# MRv2.net
KiCad netlist of a schematic drawn in Altium Designer
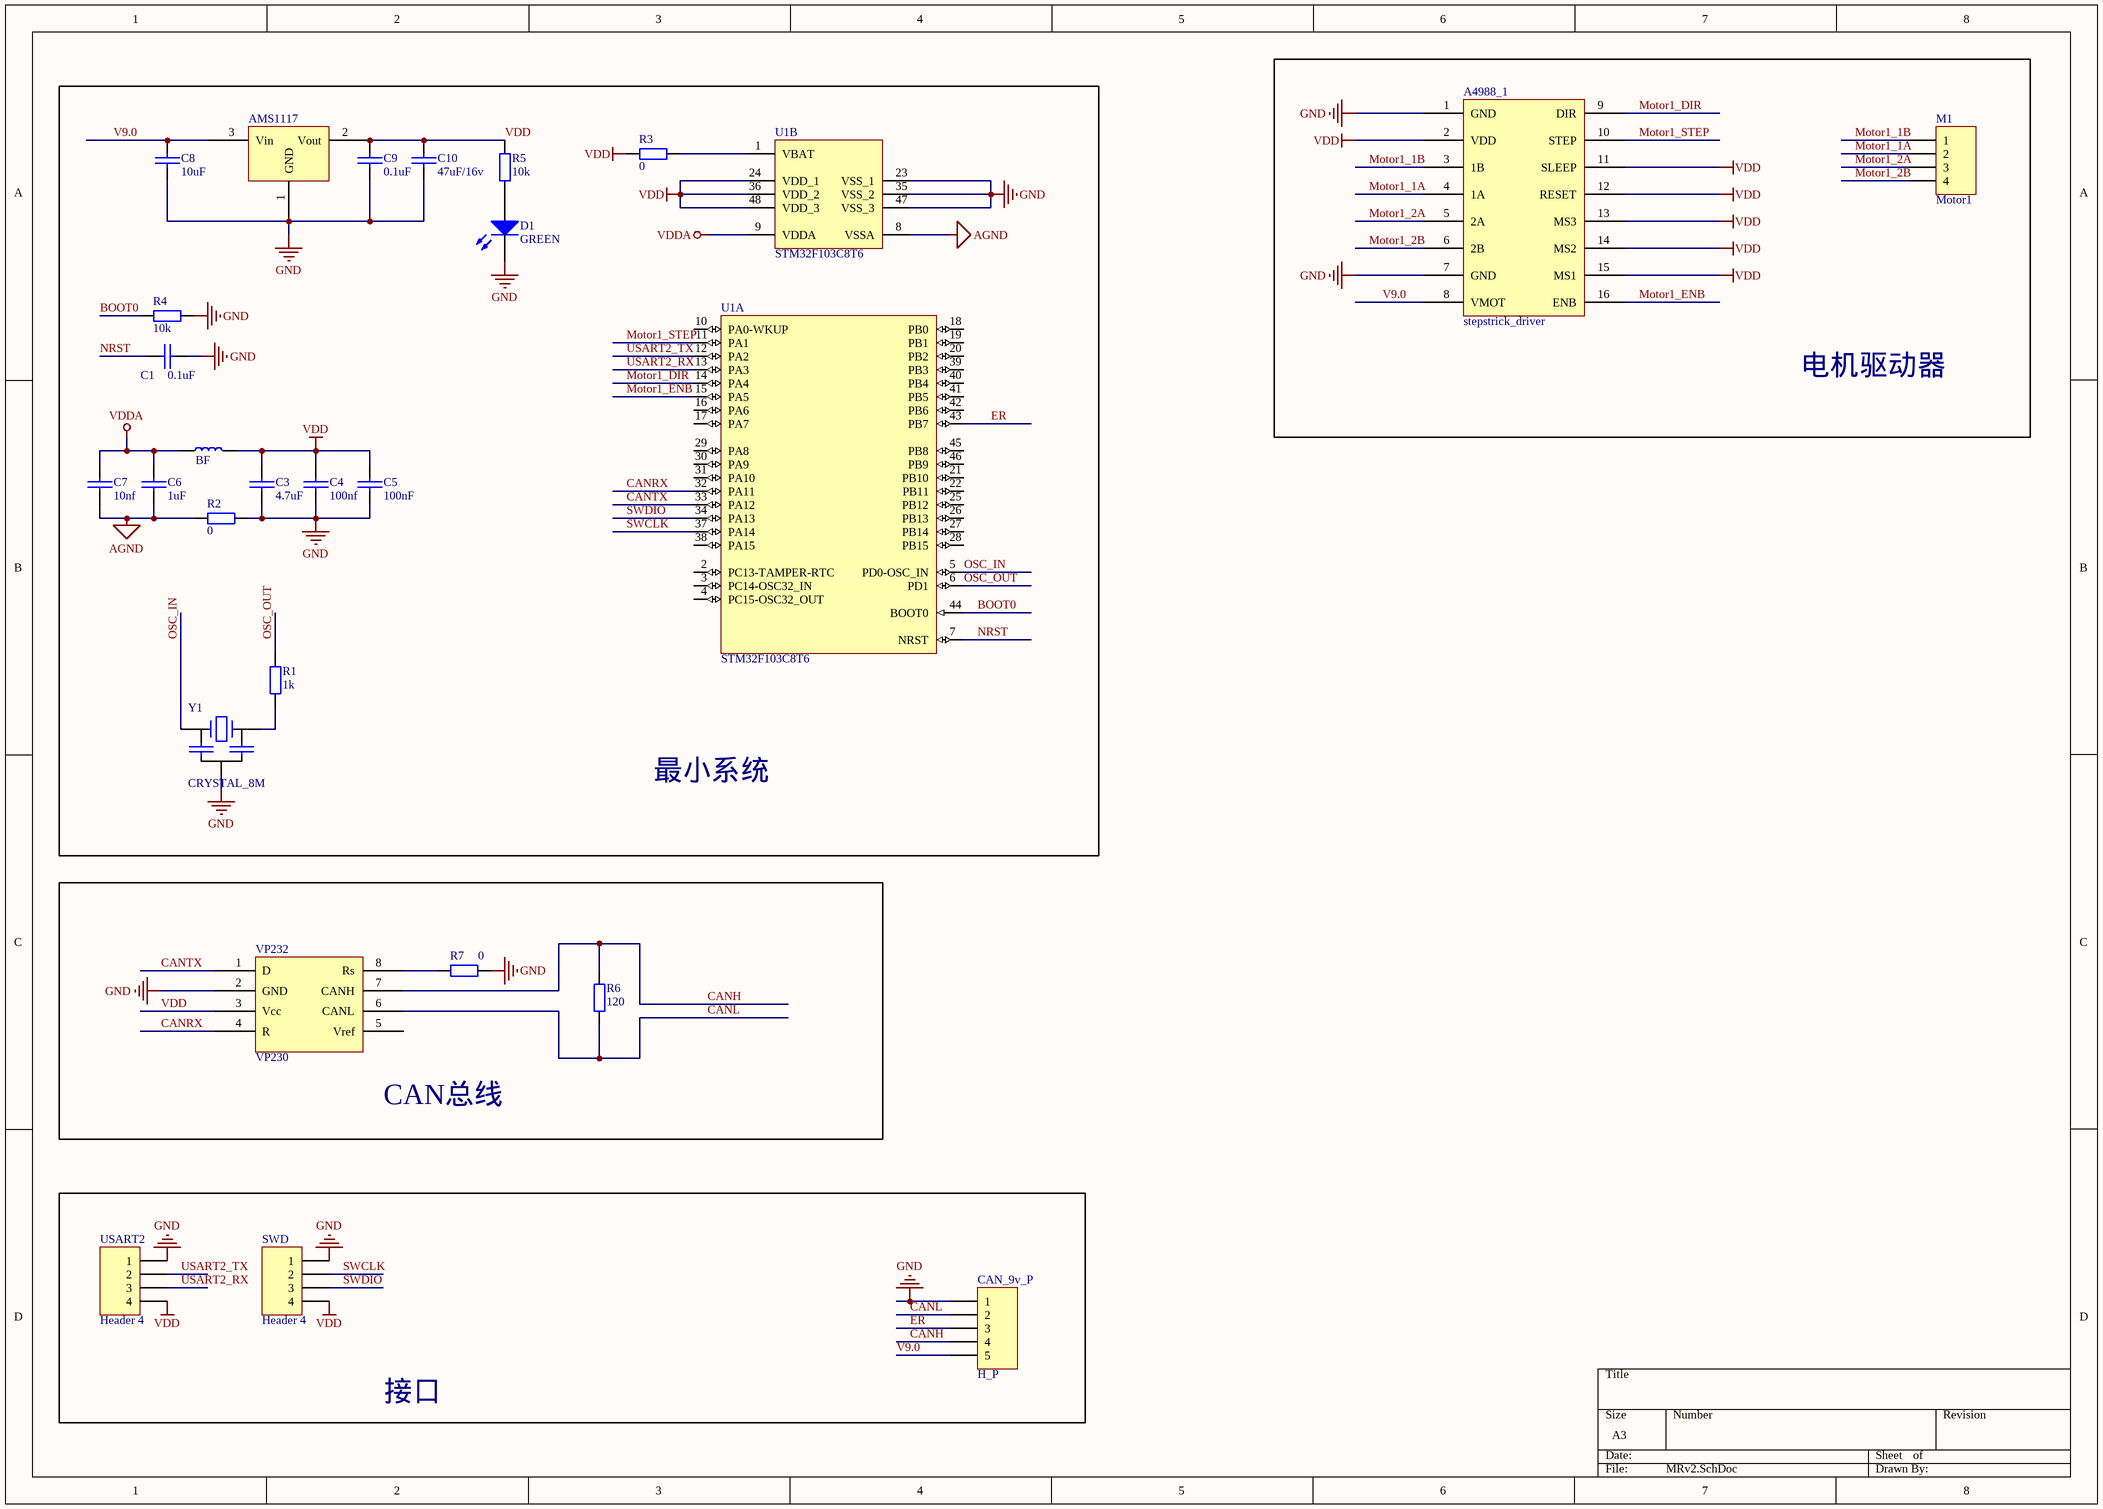
[diagram p0: MRv2.SchDoc]

(export (version "E")
  (design (tool "Eeschema 10.0.6"))
  (components
    (comp (ref "A4988_1")
      (value "stepstrick_driver")
      (footprint "A4988")
      (libsource (lib "ZYX") (part "stepstrick_driver"))
    )
    (comp (ref "AMS1117") (value "ASM1117") (footprint "SOT223") (libsource (lib "ZYX") (part "ASM1117")))
    (comp (ref "BF")
      (value "BF")
      (footprint "R1608[0603]")
      (description "磁珠")
      (libsource (lib "SkyWorks2") (part "BF"))
    )
    (comp (ref "C1")
      (value "0.1uF")
      (footprint "C1608[0603]N")
      (description "贴片无极性电容")
      (fields (field (name "Comment") "cap smd"))
      (libsource (lib "SkyWorks") (part "CAP"))
    )
    (comp (ref "C3")
      (value "4.7uF")
      (footprint "C1608[0603]N")
      (description "贴片无极性电容")
      (fields (field (name "Comment") "cap smd"))
      (libsource (lib "SkyWorks2") (part "CAP"))
    )
    (comp (ref "C4")
      (value "100nf")
      (footprint "C1608[0603]N")
      (description "贴片无极性电容")
      (fields (field (name "Comment") "cap smd"))
      (libsource (lib "SkyWorks2") (part "CAP"))
    )
    (comp (ref "C5")
      (value "100nF")
      (footprint "C1608[0603]N")
      (description "贴片无极性电容")
      (fields (field (name "Comment") "cap smd"))
      (libsource (lib "SkyWorks2") (part "CAP"))
    )
    (comp (ref "C6")
      (value "1uF")
      (footprint "C1608[0603]N")
      (description "贴片无极性电容")
      (fields (field (name "Comment") "cap smd"))
      (libsource (lib "SkyWorks2") (part "CAP"))
    )
    (comp (ref "C7")
      (value "10nf")
      (footprint "C1608[0603]N")
      (description "贴片无极性电容")
      (fields (field (name "Comment") "cap smd"))
      (libsource (lib "SkyWorks2") (part "CAP"))
    )
    (comp (ref "C8")
      (value "10uF")
      (footprint "C1608[0603]N")
      (description "贴片无极性电容")
      (fields (field (name "Comment") "cap smd"))
      (libsource (lib "SkyWorks2") (part "CAP"))
    )
    (comp (ref "C9")
      (value "0.1uF")
      (footprint "C1608[0603]N")
      (description "贴片无极性电容")
      (fields (field (name "Comment") "cap smd"))
      (libsource (lib "SkyWorks2") (part "CAP"))
    )
    (comp (ref "C10")
      (value "47uF/16v")
      (footprint "C1608[0603]N")
      (description "贴片无极性电容")
      (fields (field (name "Comment") "cap smd"))
      (libsource (lib "SkyWorks2") (part "CAP"))
    )
    (comp (ref "CAN_9v_P")
      (value "H_P")
      (footprint "HDR1X5")
      (description "Header, 5-Pin")
      (fields (field (name "PUBLISHER") "Altium Limited"))
      (libsource (lib "Miscellaneous Connectors") (part "Header 5"))
    )
    (comp (ref "D1")
      (value "GREEN")
      (footprint "D1608[0603]")
      (description "蓝色 LED")
      (fields (field (name "Comment") "LED") (field (name "PUBLISHER") "Altium Limited"))
      (libsource (lib "SkyWorks") (part "LED"))
    )
    (comp (ref "M1")
      (value "Motor1")
      (footprint "HDR1X4")
      (description "Header, 4-Pin")
      (fields (field (name "PUBLISHER") "Altium Limited"))
      (libsource (lib "") (part "Header 4_1"))
    )
    (comp (ref "R1")
      (value "1k")
      (footprint "R1608[0603]")
      (fields (field (name "Comment") "RES1"))
      (libsource (lib "SkyWorks2") (part "RES1"))
    )
    (comp (ref "R2")
      (value "0")
      (footprint "R1608[0603]")
      (fields (field (name "Comment") "RES1"))
      (libsource (lib "SkyWorks2") (part "RES1"))
    )
    (comp (ref "R3")
      (value "0")
      (footprint "1608[0603]")
      (fields (field (name "Comment") "RES1"))
      (libsource (lib "SkyWorks2") (part "RES1"))
    )
    (comp (ref "R4")
      (value "10k")
      (footprint "1608[0603]")
      (fields (field (name "Comment") "RES1"))
      (libsource (lib "SkyWorks") (part "RES1"))
    )
    (comp (ref "R5")
      (value "10k")
      (footprint "R1608[0603]")
      (fields (field (name "Comment") "RES1"))
      (libsource (lib "SkyWorks2") (part "RES1"))
    )
    (comp (ref "R6")
      (value "120")
      (footprint "R1608[0603]")
      (fields (field (name "Comment") "RES1"))
      (libsource (lib "SkyWorks2") (part "RES1"))
    )
    (comp (ref "R7")
      (value "0")
      (footprint "R1608[0603]")
      (fields (field (name "Comment") "RES1"))
      (libsource (lib "SkyWorks2") (part "RES1"))
    )
    (comp (ref "SWD")
      (value "Header 4")
      (footprint "HDR1X4")
      (description "Header, 4-Pin")
      (fields (field (name "PUBLISHER") "Altium Limited"))
      (libsource (lib "Miscellaneous Connectors") (part "Header 4"))
    )
    (comp (ref "U1")
      (value "STM32F103C8T6")
      (footprint "STMicroelectronics STM32 F1:LQFP48_N")
      (libsource (lib "STMicroelectronics STM32 F1") (part "STM32F103C8T6"))
    )
    (comp (ref "USART2")
      (value "Header 4")
      (footprint "HDR1X4")
      (description "Header, 4-Pin")
      (fields (field (name "PUBLISHER") "Altium Limited"))
      (libsource (lib "Miscellaneous Connectors") (part "Header 4"))
    )
    (comp (ref "VP232") (value "VP230") (footprint "VP232") (libsource (lib "VP232") (part "Component_1")))
    (comp (ref "Y1")
      (value "CRYSTAL_8M")
      (footprint "Crystal_C")
      (description "Crystal_8M")
      (libsource (lib "SkyWorks2") (part "CRYSTAL_C"))
    )
  )
  (nets
    (net (code "1") (name "/BOOT0") (class "Default")
      (node (ref "R4") (pin "2") (pinfunction "2_2") (pintype "passive"))
      (node (ref "U1") (pin "44") (pinfunction "BOOT0_44") (pintype "input"))
    )
    (net (code "2") (name "/CANH") (class "Default")
      (node (ref "CAN_9v_P") (pin "4") (pinfunction "4_4") (pintype "passive"))
      (node (ref "R6") (pin "2") (pinfunction "2_2") (pintype "passive"))
      (node (ref "VP232") (pin "7") (pinfunction "CANH_7") (pintype "passive"))
    )
    (net (code "3") (name "/CANL") (class "Default")
      (node (ref "CAN_9v_P") (pin "2") (pinfunction "2_2") (pintype "passive"))
      (node (ref "R6") (pin "1") (pinfunction "1_1") (pintype "passive"))
      (node (ref "VP232") (pin "6") (pinfunction "CANL_6") (pintype "passive"))
    )
    (net (code "4") (name "/CANRX") (class "Default")
      (node (ref "U1") (pin "32") (pinfunction "PA11_32") (pintype "bidirectional"))
      (node (ref "VP232") (pin "4") (pinfunction "R_4") (pintype "passive"))
    )
    (net (code "5") (name "/CANTX") (class "Default")
      (node (ref "U1") (pin "33") (pinfunction "PA12_33") (pintype "bidirectional"))
      (node (ref "VP232") (pin "1") (pinfunction "D_1") (pintype "passive"))
    )
    (net (code "6") (name "/ER") (class "Default")
      (node (ref "CAN_9v_P") (pin "3") (pinfunction "3_3") (pintype "passive"))
      (node (ref "U1") (pin "43") (pinfunction "PB7_43") (pintype "bidirectional"))
    )
    (net (code "7") (name "/Motor1_1A") (class "Default")
      (node (ref "A4988_1") (pin "4") (pinfunction "1A_4") (pintype "passive"))
      (node (ref "M1") (pin "2") (pinfunction "2_2") (pintype "passive"))
    )
    (net (code "8") (name "/Motor1_1B") (class "Default")
      (node (ref "A4988_1") (pin "3") (pinfunction "1B_3") (pintype "passive"))
      (node (ref "M1") (pin "1") (pinfunction "1_1") (pintype "passive"))
    )
    (net (code "9") (name "/Motor1_2A") (class "Default")
      (node (ref "A4988_1") (pin "5") (pinfunction "2A_5") (pintype "passive"))
      (node (ref "M1") (pin "3") (pinfunction "3_3") (pintype "passive"))
    )
    (net (code "10") (name "/Motor1_2B") (class "Default")
      (node (ref "A4988_1") (pin "6") (pinfunction "2B_6") (pintype "passive"))
      (node (ref "M1") (pin "4") (pinfunction "4_4") (pintype "passive"))
    )
    (net (code "11") (name "/Motor1_DIR") (class "Default")
      (node (ref "A4988_1") (pin "9") (pinfunction "DIR_9") (pintype "passive"))
      (node (ref "U1") (pin "14") (pinfunction "PA4_14") (pintype "bidirectional"))
    )
    (net (code "12") (name "/Motor1_ENB") (class "Default")
      (node (ref "A4988_1") (pin "16") (pinfunction "ENB_16") (pintype "passive"))
      (node (ref "U1") (pin "15") (pinfunction "PA5_15") (pintype "bidirectional"))
    )
    (net (code "13") (name "/Motor1_STEP") (class "Default")
      (node (ref "A4988_1") (pin "10") (pinfunction "STEP_10") (pintype "passive"))
      (node (ref "U1") (pin "11") (pinfunction "PA1_11") (pintype "bidirectional"))
    )
    (net (code "14") (name "/NRST") (class "Default")
      (node (ref "C1") (pin "2") (pinfunction "2_2") (pintype "passive"))
      (node (ref "U1") (pin "7") (pinfunction "NRST_7") (pintype "bidirectional"))
    )
    (net (code "15") (name "/OSC_IN") (class "Default")
      (node (ref "U1") (pin "5") (pinfunction "PD0-OSC_IN_5") (pintype "bidirectional"))
      (node (ref "Y1") (pin "1") (pinfunction "1_1") (pintype "passive"))
    )
    (net (code "16") (name "/OSC_OUT") (class "Default")
      (node (ref "R1") (pin "2") (pinfunction "2_2") (pintype "passive"))
      (node (ref "U1") (pin "6") (pinfunction "PD1_6") (pintype "bidirectional"))
    )
    (net (code "17") (name "/SWCLK") (class "Default")
      (node (ref "SWD") (pin "2") (pinfunction "2_2") (pintype "passive"))
      (node (ref "U1") (pin "37") (pinfunction "PA14_37") (pintype "bidirectional"))
    )
    (net (code "18") (name "/SWDIO") (class "Default")
      (node (ref "SWD") (pin "3") (pinfunction "3_3") (pintype "passive"))
      (node (ref "U1") (pin "34") (pinfunction "PA13_34") (pintype "bidirectional"))
    )
    (net (code "19") (name "/USART2_RX") (class "Default")
      (node (ref "U1") (pin "13") (pinfunction "PA3_13") (pintype "bidirectional"))
      (node (ref "USART2") (pin "3") (pinfunction "3_3") (pintype "passive"))
    )
    (net (code "20") (name "/USART2_TX") (class "Default")
      (node (ref "U1") (pin "12") (pinfunction "PA2_12") (pintype "bidirectional"))
      (node (ref "USART2") (pin "2") (pinfunction "2_2") (pintype "passive"))
    )
    (net (code "21") (name "/V9.0") (class "Default")
      (node (ref "A4988_1") (pin "8") (pinfunction "VMOT_8") (pintype "passive"))
      (node (ref "AMS1117") (pin "3") (pinfunction "Vin_3") (pintype "passive"))
      (node (ref "C8") (pin "1") (pinfunction "1_1") (pintype "passive"))
      (node (ref "CAN_9v_P") (pin "5") (pinfunction "5_5") (pintype "passive"))
    )
    (net (code "22") (name "AGND") (class "Default")
      (node (ref "C6") (pin "2") (pinfunction "2_2") (pintype "passive"))
      (node (ref "C7") (pin "2") (pinfunction "2_2") (pintype "passive"))
      (node (ref "R2") (pin "1") (pinfunction "1_1") (pintype "passive"))
      (node (ref "U1") (pin "8") (pinfunction "VSSA_8") (pintype "power_in"))
    )
    (net (code "23") (name "GND") (class "Default")
      (node (ref "A4988_1") (pin "1") (pinfunction "GND_1") (pintype "passive"))
      (node (ref "A4988_1") (pin "7") (pinfunction "GND_7") (pintype "passive"))
      (node (ref "AMS1117") (pin "1") (pinfunction "GND_1") (pintype "passive"))
      (node (ref "C1") (pin "1") (pinfunction "1_1") (pintype "passive"))
      (node (ref "C10") (pin "2") (pinfunction "2_2") (pintype "passive"))
      (node (ref "C3") (pin "2") (pinfunction "2_2") (pintype "passive"))
      (node (ref "C4") (pin "2") (pinfunction "2_2") (pintype "passive"))
      (node (ref "C5") (pin "2") (pinfunction "2_2") (pintype "passive"))
      (node (ref "C8") (pin "2") (pinfunction "2_2") (pintype "passive"))
      (node (ref "C9") (pin "2") (pinfunction "2_2") (pintype "passive"))
      (node (ref "CAN_9v_P") (pin "1") (pinfunction "1_1") (pintype "passive"))
      (node (ref "D1") (pin "2") (pinfunction "K_2") (pintype "passive"))
      (node (ref "R2") (pin "2") (pinfunction "2_2") (pintype "passive"))
      (node (ref "R4") (pin "1") (pinfunction "1_1") (pintype "passive"))
      (node (ref "R7") (pin "2") (pinfunction "2_2") (pintype "passive"))
      (node (ref "SWD") (pin "1") (pinfunction "1_1") (pintype "passive"))
      (node (ref "U1") (pin "23") (pinfunction "VSS_1_23") (pintype "power_in"))
      (node (ref "U1") (pin "35") (pinfunction "VSS_2_35") (pintype "power_in"))
      (node (ref "U1") (pin "47") (pinfunction "VSS_3_47") (pintype "power_in"))
      (node (ref "USART2") (pin "1") (pinfunction "1_1") (pintype "passive"))
      (node (ref "VP232") (pin "2") (pinfunction "GND_2") (pintype "passive"))
      (node (ref "Y1") (pin "2") (pinfunction "GND_2") (pintype "passive"))
    )
    (net (code "24") (name "Net-(D1-A)") (class "Default")
      (node (ref "D1") (pin "1") (pinfunction "A_1") (pintype "passive"))
      (node (ref "R5") (pin "1") (pinfunction "1_1") (pintype "passive"))
    )
    (net (code "25") (name "Net-(R1-Pad1)") (class "Default")
      (node (ref "R1") (pin "1") (pinfunction "1_1") (pintype "passive"))
      (node (ref "Y1") (pin "3") (pinfunction "3_3") (pintype "passive"))
    )
    (net (code "26") (name "Net-(U1B-VBAT)") (class "Default")
      (node (ref "R3") (pin "2") (pinfunction "2_2") (pintype "passive"))
      (node (ref "U1") (pin "1") (pinfunction "VBAT_1") (pintype "power_in"))
    )
    (net (code "27") (name "Net-(VP232-Rs)") (class "Default")
      (node (ref "R7") (pin "1") (pinfunction "1_1") (pintype "passive"))
      (node (ref "VP232") (pin "8") (pinfunction "Rs_8") (pintype "passive"))
    )
    (net (code "28") (name "VDD") (class "Default")
      (node (ref "A4988_1") (pin "11") (pinfunction "SLEEP_11") (pintype "passive"))
      (node (ref "A4988_1") (pin "12") (pinfunction "RESET_12") (pintype "passive"))
      (node (ref "A4988_1") (pin "13") (pinfunction "MS3_13") (pintype "passive"))
      (node (ref "A4988_1") (pin "14") (pinfunction "MS2_14") (pintype "passive"))
      (node (ref "A4988_1") (pin "15") (pinfunction "MS1_15") (pintype "passive"))
      (node (ref "A4988_1") (pin "2") (pinfunction "VDD_2") (pintype "passive"))
      (node (ref "AMS1117") (pin "2") (pinfunction "Vout_2") (pintype "passive"))
      (node (ref "BF") (pin "2") (pinfunction "2_2") (pintype "passive"))
      (node (ref "C10") (pin "1") (pinfunction "1_1") (pintype "passive"))
      (node (ref "C3") (pin "1") (pinfunction "1_1") (pintype "passive"))
      (node (ref "C4") (pin "1") (pinfunction "1_1") (pintype "passive"))
      (node (ref "C5") (pin "1") (pinfunction "1_1") (pintype "passive"))
      (node (ref "C9") (pin "1") (pinfunction "1_1") (pintype "passive"))
      (node (ref "R3") (pin "1") (pinfunction "1_1") (pintype "passive"))
      (node (ref "R5") (pin "2") (pinfunction "2_2") (pintype "passive"))
      (node (ref "SWD") (pin "4") (pinfunction "4_4") (pintype "passive"))
      (node (ref "U1") (pin "24") (pinfunction "VDD_1_24") (pintype "power_in"))
      (node (ref "U1") (pin "36") (pinfunction "VDD_2_36") (pintype "power_in"))
      (node (ref "U1") (pin "48") (pinfunction "VDD_3_48") (pintype "power_in"))
      (node (ref "USART2") (pin "4") (pinfunction "4_4") (pintype "passive"))
      (node (ref "VP232") (pin "3") (pinfunction "Vcc_3") (pintype "passive"))
    )
    (net (code "29") (name "VDDA") (class "Default")
      (node (ref "BF") (pin "1") (pinfunction "1_1") (pintype "passive"))
      (node (ref "C6") (pin "1") (pinfunction "1_1") (pintype "passive"))
      (node (ref "C7") (pin "1") (pinfunction "1_1") (pintype "passive"))
      (node (ref "U1") (pin "9") (pinfunction "VDDA_9") (pintype "power_in"))
    )
    (net (code "30") (name "unconnected-(U1A-PA0-WKUP-Pad10)") (class "Default")
      (node (ref "U1") (pin "10") (pinfunction "PA0-WKUP_10") (pintype "bidirectional"))
    )
    (net (code "31") (name "unconnected-(U1A-PA6-Pad16)") (class "Default")
      (node (ref "U1") (pin "16") (pinfunction "PA6_16") (pintype "bidirectional"))
    )
    (net (code "32") (name "unconnected-(U1A-PA7-Pad17)") (class "Default")
      (node (ref "U1") (pin "17") (pinfunction "PA7_17") (pintype "bidirectional"))
    )
    (net (code "33") (name "unconnected-(U1A-PA8-Pad29)") (class "Default")
      (node (ref "U1") (pin "29") (pinfunction "PA8_29") (pintype "bidirectional"))
    )
    (net (code "34") (name "unconnected-(U1A-PA9-Pad30)") (class "Default")
      (node (ref "U1") (pin "30") (pinfunction "PA9_30") (pintype "bidirectional"))
    )
    (net (code "35") (name "unconnected-(U1A-PA10-Pad31)") (class "Default")
      (node (ref "U1") (pin "31") (pinfunction "PA10_31") (pintype "bidirectional"))
    )
    (net (code "36") (name "unconnected-(U1A-PA15-Pad38)") (class "Default")
      (node (ref "U1") (pin "38") (pinfunction "PA15_38") (pintype "bidirectional"))
    )
    (net (code "37") (name "unconnected-(U1A-PB0-Pad18)") (class "Default")
      (node (ref "U1") (pin "18") (pinfunction "PB0_18") (pintype "bidirectional"))
    )
    (net (code "38") (name "unconnected-(U1A-PB1-Pad19)") (class "Default")
      (node (ref "U1") (pin "19") (pinfunction "PB1_19") (pintype "bidirectional"))
    )
    (net (code "39") (name "unconnected-(U1A-PB2-Pad20)") (class "Default")
      (node (ref "U1") (pin "20") (pinfunction "PB2_20") (pintype "bidirectional"))
    )
    (net (code "40") (name "unconnected-(U1A-PB3-Pad39)") (class "Default")
      (node (ref "U1") (pin "39") (pinfunction "PB3_39") (pintype "bidirectional"))
    )
    (net (code "41") (name "unconnected-(U1A-PB4-Pad40)") (class "Default")
      (node (ref "U1") (pin "40") (pinfunction "PB4_40") (pintype "bidirectional"))
    )
    (net (code "42") (name "unconnected-(U1A-PB5-Pad41)") (class "Default")
      (node (ref "U1") (pin "41") (pinfunction "PB5_41") (pintype "bidirectional"))
    )
    (net (code "43") (name "unconnected-(U1A-PB6-Pad42)") (class "Default")
      (node (ref "U1") (pin "42") (pinfunction "PB6_42") (pintype "bidirectional"))
    )
    (net (code "44") (name "unconnected-(U1A-PB8-Pad45)") (class "Default")
      (node (ref "U1") (pin "45") (pinfunction "PB8_45") (pintype "bidirectional"))
    )
    (net (code "45") (name "unconnected-(U1A-PB9-Pad46)") (class "Default")
      (node (ref "U1") (pin "46") (pinfunction "PB9_46") (pintype "bidirectional"))
    )
    (net (code "46") (name "unconnected-(U1A-PB10-Pad21)") (class "Default")
      (node (ref "U1") (pin "21") (pinfunction "PB10_21") (pintype "bidirectional"))
    )
    (net (code "47") (name "unconnected-(U1A-PB11-Pad22)") (class "Default")
      (node (ref "U1") (pin "22") (pinfunction "PB11_22") (pintype "bidirectional"))
    )
    (net (code "48") (name "unconnected-(U1A-PB12-Pad25)") (class "Default")
      (node (ref "U1") (pin "25") (pinfunction "PB12_25") (pintype "bidirectional"))
    )
    (net (code "49") (name "unconnected-(U1A-PB13-Pad26)") (class "Default")
      (node (ref "U1") (pin "26") (pinfunction "PB13_26") (pintype "bidirectional"))
    )
    (net (code "50") (name "unconnected-(U1A-PB14-Pad27)") (class "Default")
      (node (ref "U1") (pin "27") (pinfunction "PB14_27") (pintype "bidirectional"))
    )
    (net (code "51") (name "unconnected-(U1A-PB15-Pad28)") (class "Default")
      (node (ref "U1") (pin "28") (pinfunction "PB15_28") (pintype "bidirectional"))
    )
    (net (code "52") (name "unconnected-(U1A-PC13-TAMPER-RTC-Pad2)") (class "Default")
      (node (ref "U1") (pin "2") (pinfunction "PC13-TAMPER-RTC_2") (pintype "bidirectional"))
    )
    (net (code "53") (name "unconnected-(U1A-PC14-OSC32_IN-Pad3)") (class "Default")
      (node (ref "U1") (pin "3") (pinfunction "PC14-OSC32_IN_3") (pintype "bidirectional"))
    )
    (net (code "54") (name "unconnected-(U1A-PC15-OSC32_OUT-Pad4)") (class "Default")
      (node (ref "U1") (pin "4") (pinfunction "PC15-OSC32_OUT_4") (pintype "bidirectional"))
    )
    (net (code "55") (name "unconnected-(VP232-Vref-Pad5)") (class "Default")
      (node (ref "VP232") (pin "5") (pinfunction "Vref_5") (pintype "passive"))
    )
  )
)
